# FishTankControllerV2.net
KiCad netlist of a schematic drawn in EAGLE
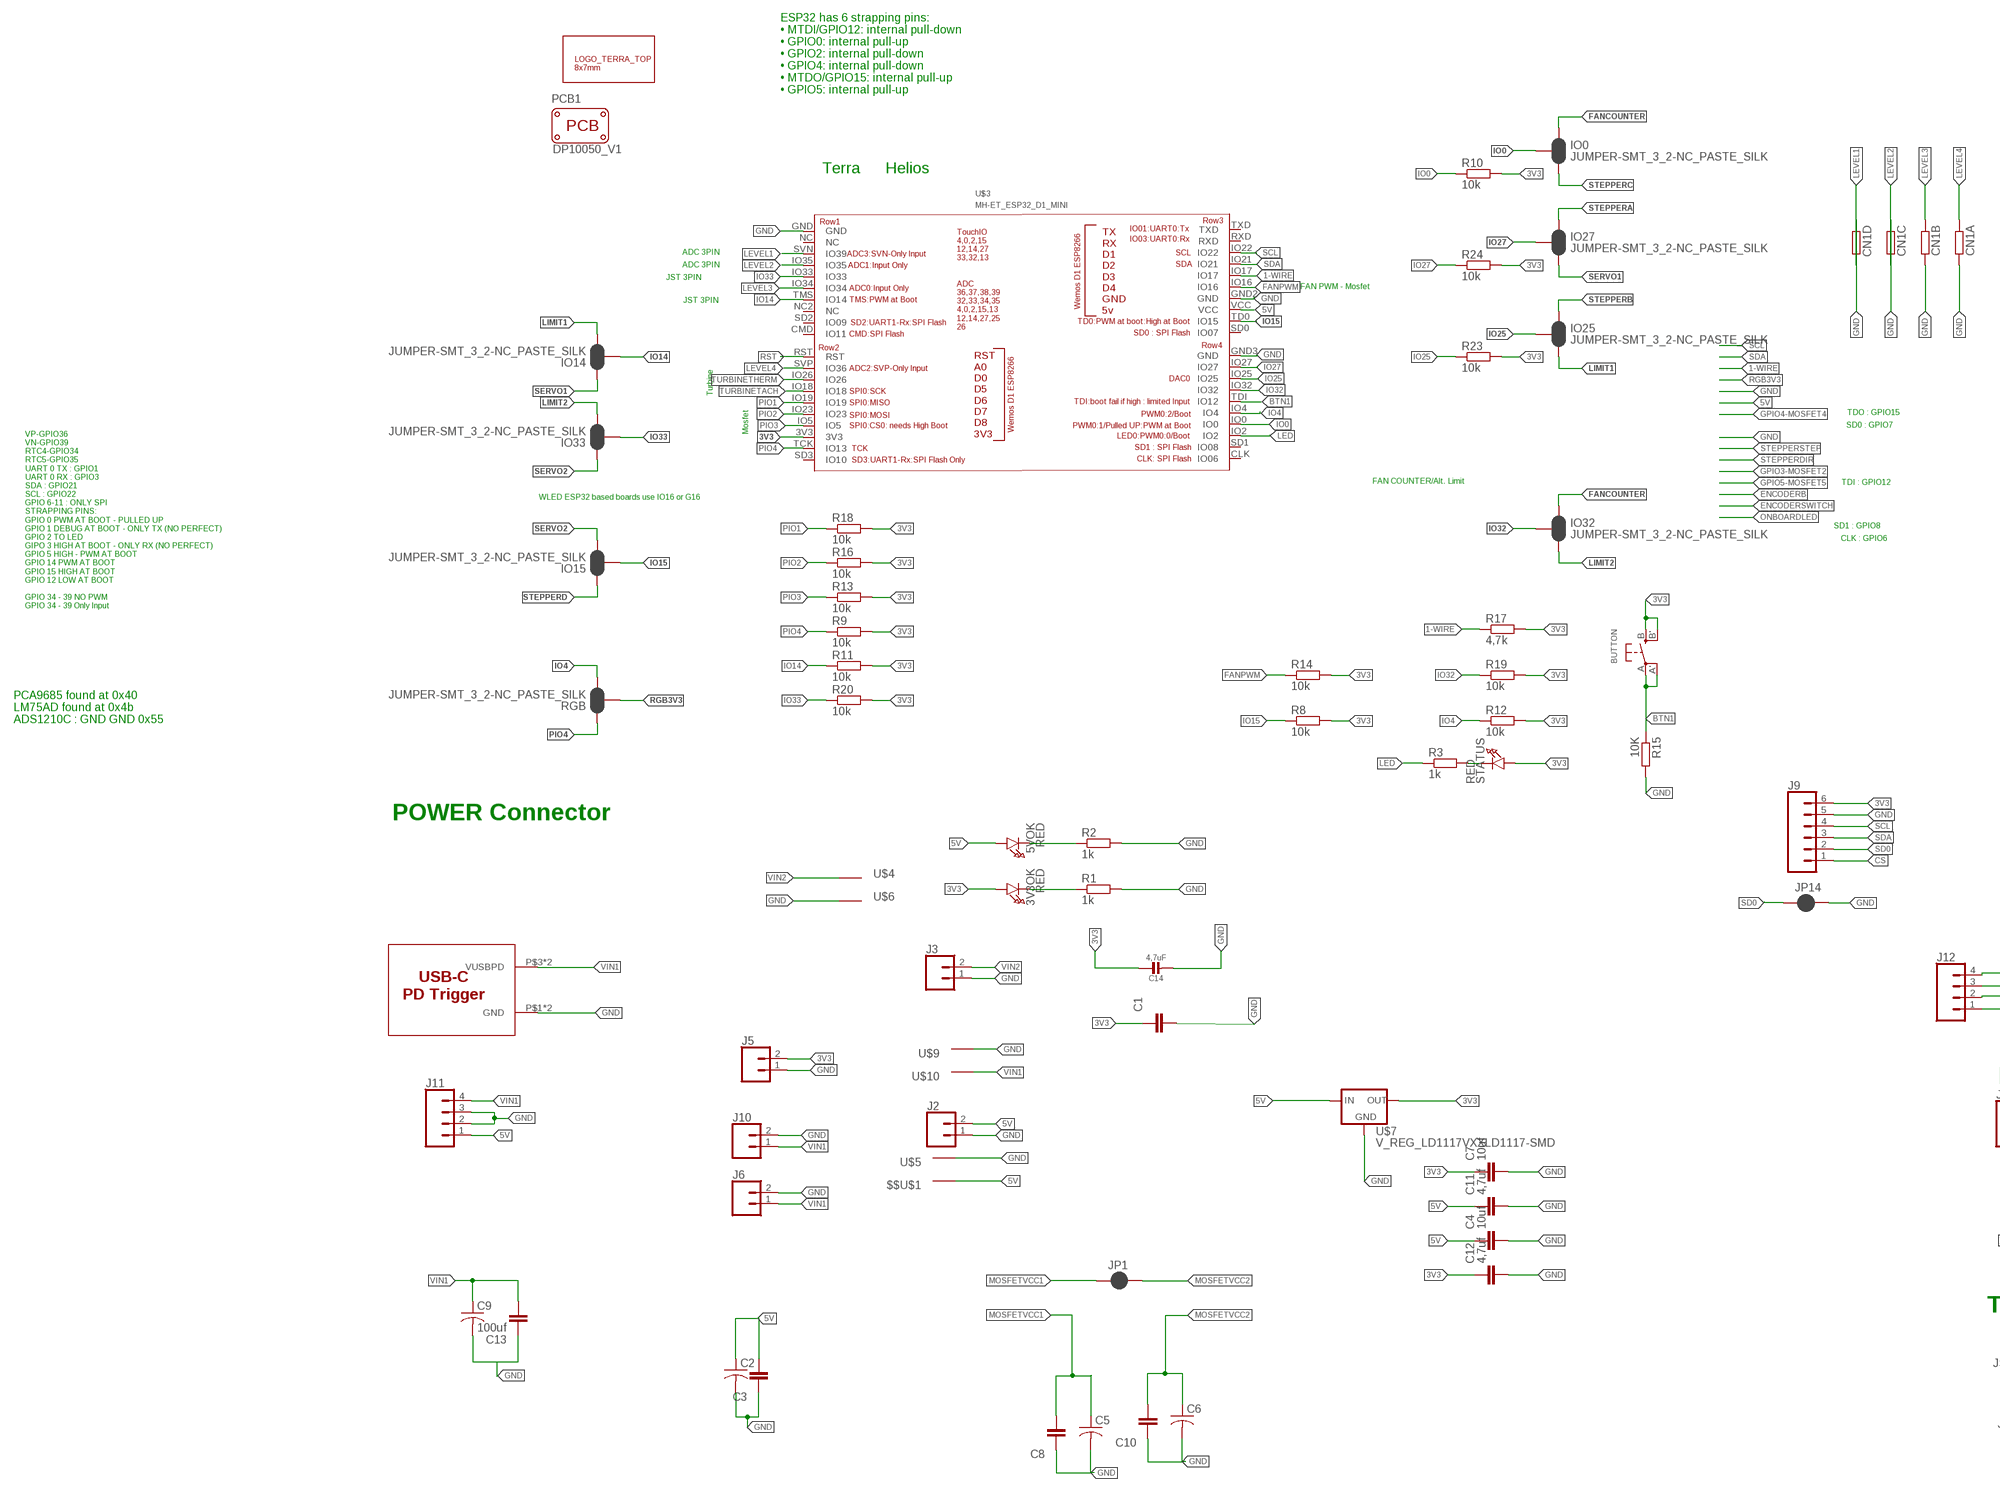
[diagram p0: schematic, sheet 1, part 1 of 2]
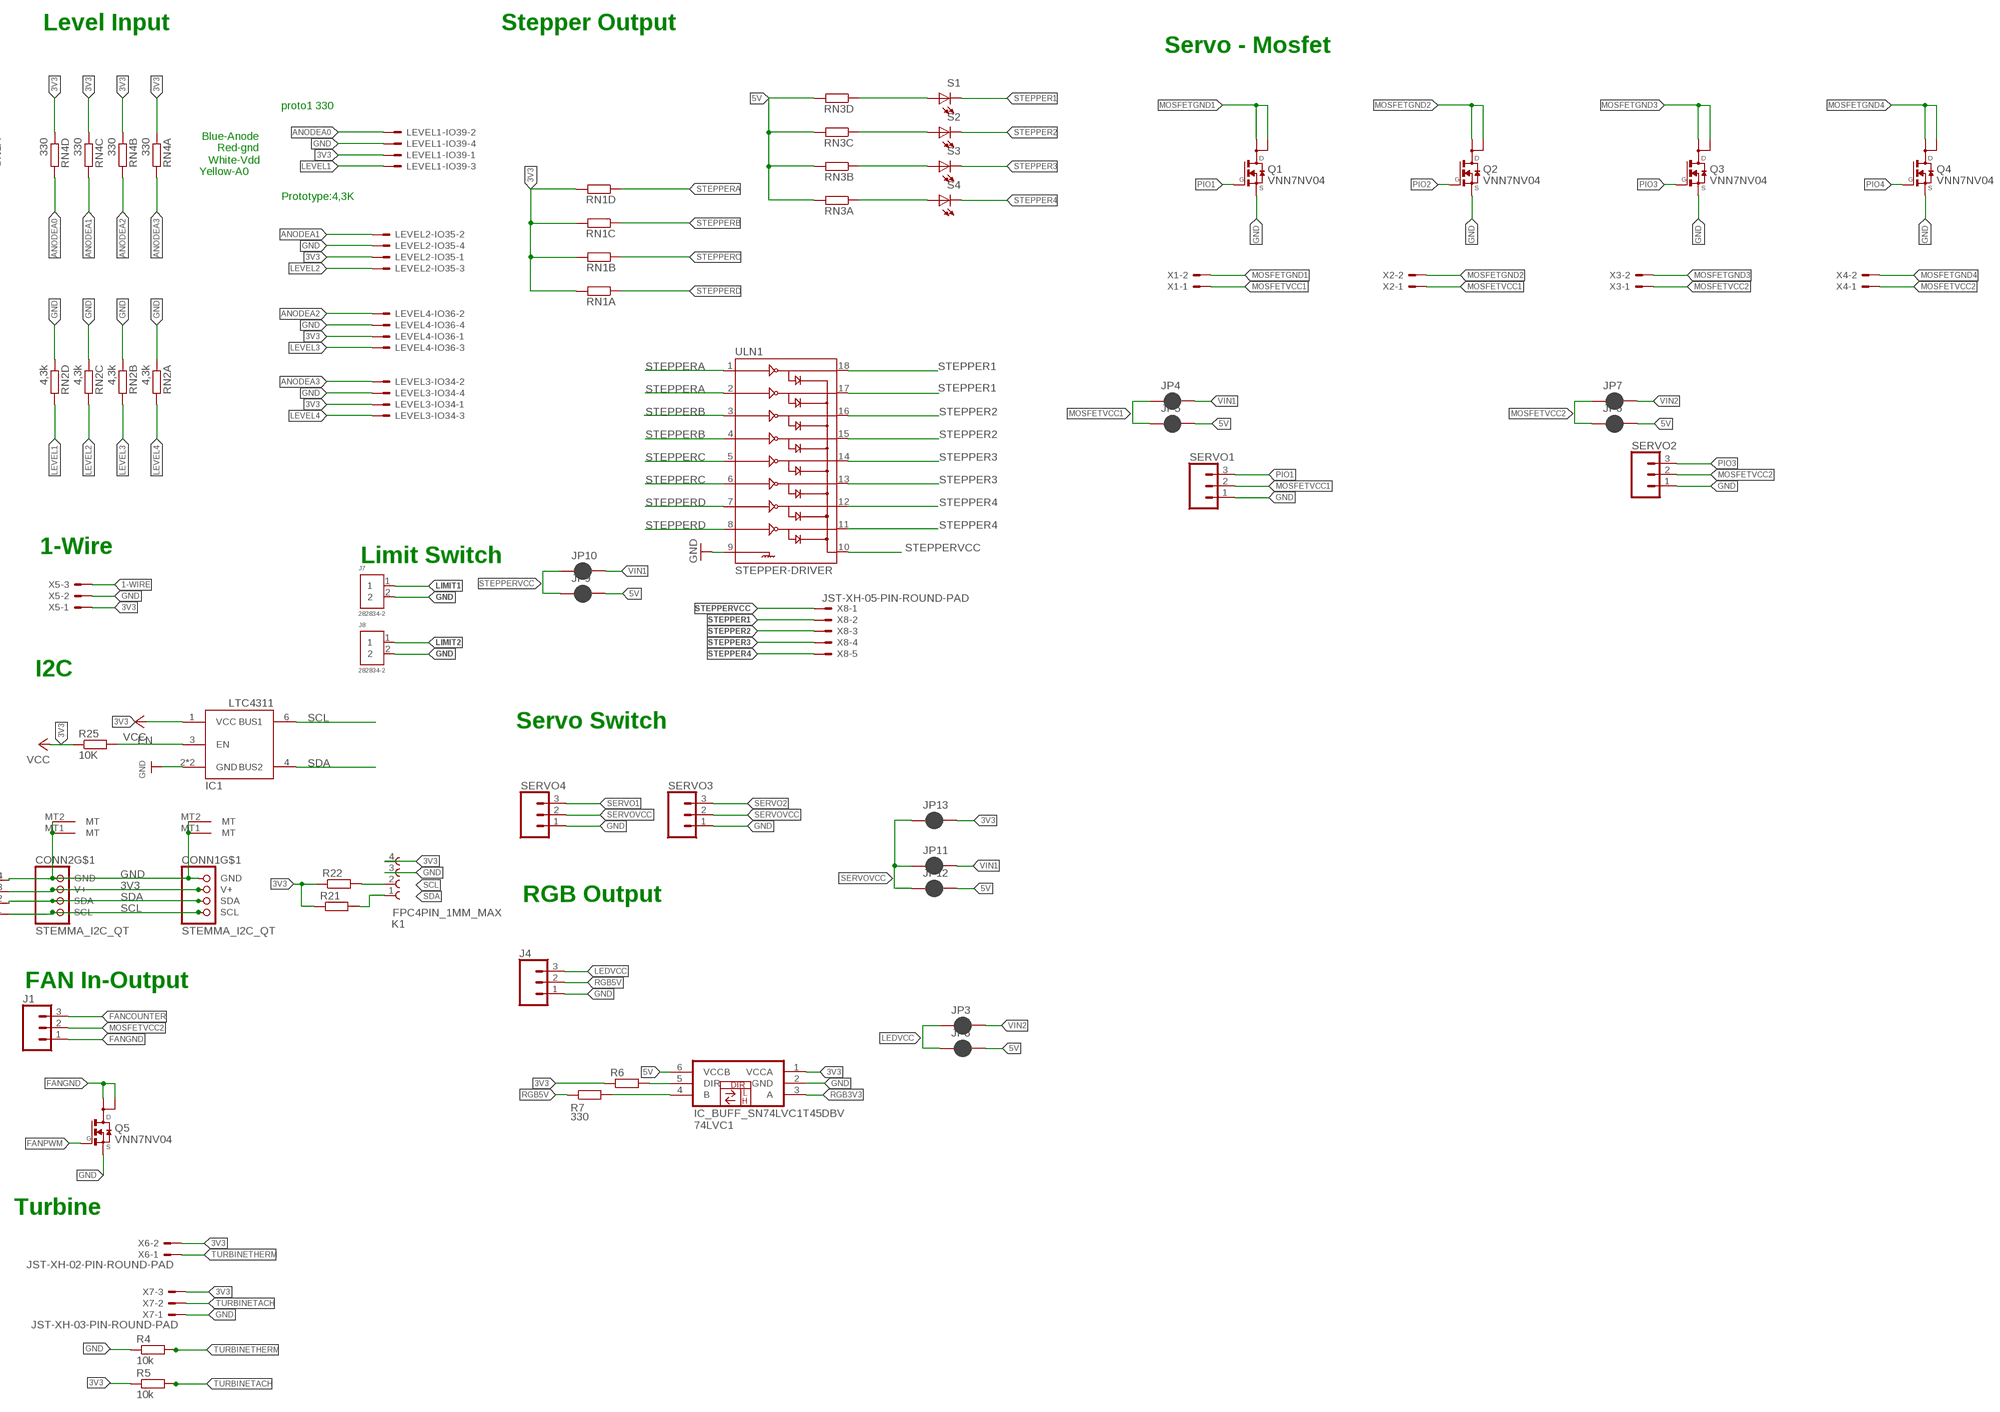
[diagram p1: schematic, sheet 1, part 2 of 2]

(export (version "E")
  (design (tool "Eeschema 10.0.6"))
  (components
    (comp (ref "$$U$1")
      (value "TESTHOOK")
      (footprint "eagle-import:TESTHOOK")
      (libsource (lib "eagle-import") (part "TESTHOOK"))
    )
    (comp (ref "3V3OK")
      (value "RED")
      (footprint "eagle-import:CHIPLED_0805")
      (libsource (lib "eagle-import") (part "LED0805"))
    )
    (comp (ref "5VOK")
      (value "RED")
      (footprint "eagle-import:CHIPLED_0805")
      (libsource (lib "eagle-import") (part "LED0805"))
    )
    (comp (ref "74LVC1")
      (value "IC_BUFF_SN74LVC1T45DBV")
      (footprint "eagle-import:DBV-R-PDSO-G6")
      (libsource (lib "eagle-import") (part "IC_BUFF_SN74LVC1T45DBV"))
    )
    (comp (ref "BUTTON")
      (value "KMR2")
      (footprint "eagle-import:BTN_KMR2_4.6X2.8")
      (libsource (lib "eagle-import") (part "SWITCH_TACT_SMT4.6X2.8"))
    )
    (comp (ref "C1")
      (value "CAPACITOR_NPOL-0805")
      (footprint "eagle-import:C805")
      (libsource (lib "eagle-import") (part "CAPACITOR_NPOL-0805"))
    )
    (comp (ref "C2")
      (value "C-USC1210")
      (footprint "eagle-import:C1210")
      (libsource (lib "eagle-import") (part "C-USC1210"))
    )
    (comp (ref "C3")
      (value "CAPACITOR_NPOL-0805")
      (footprint "eagle-import:C805")
      (libsource (lib "eagle-import") (part "CAPACITOR_NPOL-0805"))
    )
    (comp (ref "C4")
      (value "10uf")
      (footprint "eagle-import:C805")
      (libsource (lib "eagle-import") (part "CAPACITOR_NPOL-0805"))
    )
    (comp (ref "C5")
      (value "C-USC1210")
      (footprint "eagle-import:C1210")
      (libsource (lib "eagle-import") (part "C-USC1210"))
    )
    (comp (ref "C6")
      (value "C-USC1210")
      (footprint "eagle-import:C1210")
      (libsource (lib "eagle-import") (part "C-USC1210"))
    )
    (comp (ref "C7")
      (value "10uf")
      (footprint "eagle-import:C805")
      (libsource (lib "eagle-import") (part "CAPACITOR_NPOL-0805"))
    )
    (comp (ref "C8")
      (value "CAPACITOR_NPOL-0805")
      (footprint "eagle-import:C805")
      (libsource (lib "eagle-import") (part "CAPACITOR_NPOL-0805"))
    )
    (comp (ref "C9")
      (value "100uf")
      (footprint "eagle-import:C1210")
      (libsource (lib "eagle-import") (part "C-USC1210"))
    )
    (comp (ref "C10")
      (value "CAPACITOR_NPOL-0805")
      (footprint "eagle-import:C805")
      (libsource (lib "eagle-import") (part "CAPACITOR_NPOL-0805"))
    )
    (comp (ref "C11")
      (value "4,7uf")
      (footprint "eagle-import:C805")
      (libsource (lib "eagle-import") (part "CAPACITOR_NPOL-0805"))
    )
    (comp (ref "C12")
      (value "4,7uf")
      (footprint "eagle-import:C805")
      (libsource (lib "eagle-import") (part "CAPACITOR_NPOL-0805"))
    )
    (comp (ref "C13")
      (value "CAPACITOR_NPOL-0805")
      (footprint "eagle-import:C805")
      (libsource (lib "eagle-import") (part "CAPACITOR_NPOL-0805"))
    )
    (comp (ref "C14")
      (value "4,7uF")
      (footprint "eagle-import:0805-NO")
      (libsource (lib "eagle-import") (part "CAP_CERAMIC0805-NOOUTLINE"))
    )
    (comp (ref "CN1")
      (value "RESISTOR_ARRAY_4")
      (footprint "eagle-import:RN8P-4R-CRA06S")
      (libsource (lib "eagle-import") (part "RESISTOR_ARRAY_4"))
    )
    (comp (ref "CONN1")
      (value "STEMMA_I2C_QT")
      (footprint "eagle-import:JST_SH4")
      (libsource (lib "eagle-import") (part "STEMMA_I2C_QT"))
    )
    (comp (ref "CONN2")
      (value "STEMMA_I2C_QT")
      (footprint "eagle-import:JST_SH4")
      (libsource (lib "eagle-import") (part "STEMMA_I2C_QT"))
    )
    (comp (ref "IC1")
      (value "LTC4311_SC70")
      (footprint "eagle-import:SC70-6L")
      (libsource (lib "eagle-import") (part "LTC4311_SC70"))
    )
    (comp (ref "IO0")
      (value "JUMPER-SMT_3_2-NC_PASTE_SILK")
      (footprint "eagle-import:SMT-JUMPER_3_2-NC_PASTE_SILK")
      (libsource (lib "eagle-import") (part "JUMPER-SMT_3_2-NC_PASTE_SILK"))
    )
    (comp (ref "IO14")
      (value "JUMPER-SMT_3_2-NC_PASTE_SILK")
      (footprint "eagle-import:SMT-JUMPER_3_2-NC_PASTE_SILK")
      (libsource (lib "eagle-import") (part "JUMPER-SMT_3_2-NC_PASTE_SILK"))
    )
    (comp (ref "IO15")
      (value "JUMPER-SMT_3_2-NC_PASTE_SILK")
      (footprint "eagle-import:SMT-JUMPER_3_2-NC_PASTE_SILK")
      (libsource (lib "eagle-import") (part "JUMPER-SMT_3_2-NC_PASTE_SILK"))
    )
    (comp (ref "IO25")
      (value "JUMPER-SMT_3_2-NC_PASTE_SILK")
      (footprint "eagle-import:SMT-JUMPER_3_2-NC_PASTE_SILK")
      (libsource (lib "eagle-import") (part "JUMPER-SMT_3_2-NC_PASTE_SILK"))
    )
    (comp (ref "IO27")
      (value "JUMPER-SMT_3_2-NC_PASTE_SILK")
      (footprint "eagle-import:SMT-JUMPER_3_2-NC_PASTE_SILK")
      (libsource (lib "eagle-import") (part "JUMPER-SMT_3_2-NC_PASTE_SILK"))
    )
    (comp (ref "IO32")
      (value "JUMPER-SMT_3_2-NC_PASTE_SILK")
      (footprint "eagle-import:SMT-JUMPER_3_2-NC_PASTE_SILK")
      (libsource (lib "eagle-import") (part "JUMPER-SMT_3_2-NC_PASTE_SILK"))
    )
    (comp (ref "IO33")
      (value "JUMPER-SMT_3_2-NC_PASTE_SILK")
      (footprint "eagle-import:SMT-JUMPER_3_2-NC_PASTE_SILK")
      (libsource (lib "eagle-import") (part "JUMPER-SMT_3_2-NC_PASTE_SILK"))
    )
    (comp (ref "J1")
      (value "CONN_03POLAR")
      (footprint "eagle-import:MOLEX-1X3")
      (libsource (lib "eagle-import") (part "CONN_03POLAR"))
    )
    (comp (ref "J2")
      (value "CONN_02POLAR")
      (footprint "eagle-import:MOLEX-1X2")
      (libsource (lib "eagle-import") (part "CONN_02POLAR"))
    )
    (comp (ref "J3")
      (value "CONN_02POLAR")
      (footprint "eagle-import:MOLEX-1X2")
      (libsource (lib "eagle-import") (part "CONN_02POLAR"))
    )
    (comp (ref "J4")
      (value "CONN_03SCREW")
      (footprint "eagle-import:SCREWTERMINAL-3.5MM-3")
      (libsource (lib "eagle-import") (part "CONN_03SCREW"))
    )
    (comp (ref "J5")
      (value "CONN_02POLAR")
      (footprint "eagle-import:MOLEX-1X2")
      (libsource (lib "eagle-import") (part "CONN_02POLAR"))
    )
    (comp (ref "J6")
      (value "CONN_023.5MM")
      (footprint "eagle-import:SCREWTERMINAL-3.5MM-2")
      (libsource (lib "eagle-import") (part "CONN_023.5MM"))
    )
    (comp (ref "J7")
      (value "282834-2")
      (footprint "eagle-import:CONN_282834-2")
      (fields (field (name "MF") "TE Connectivity"))
      (libsource (lib "eagle-import") (part "282834-2"))
    )
    (comp (ref "J8")
      (value "282834-2")
      (footprint "eagle-import:CONN_282834-2")
      (fields (field (name "MF") "TE Connectivity"))
      (libsource (lib "eagle-import") (part "282834-2"))
    )
    (comp (ref "J9")
      (value "CONN_06NO_SILK_FEMALE_PTH")
      (footprint "eagle-import:1X06_NO_SILK")
      (libsource (lib "eagle-import") (part "CONN_06NO_SILK_FEMALE_PTH"))
    )
    (comp (ref "J10")
      (value "CONN_023.5MM")
      (footprint "eagle-import:SCREWTERMINAL-3.5MM-2")
      (libsource (lib "eagle-import") (part "CONN_023.5MM"))
    )
    (comp (ref "J11")
      (value "CONN_04")
      (footprint "eagle-import:1X04")
      (libsource (lib "eagle-import") (part "CONN_04"))
    )
    (comp (ref "J12")
      (value "CONN_04JST-PH-4-1.0MM")
      (footprint "eagle-import:JST-4-SMD-VERT-1.0MM")
      (libsource (lib "eagle-import") (part "CONN_04JST-PH-4-1.0MM"))
    )
    (comp (ref "JP1")
      (value "JUMPER-SMT_2_NC_PASTE_SILK")
      (footprint "eagle-import:SMT-JUMPER_2_NC_PASTE_SILK")
      (libsource (lib "eagle-import") (part "JUMPER-SMT_2_NC_PASTE_SILK"))
    )
    (comp (ref "JP3")
      (value "JUMPER-SMT_2_NC_PASTE_SILK")
      (footprint "eagle-import:SMT-JUMPER_2_NC_PASTE_SILK")
      (libsource (lib "eagle-import") (part "JUMPER-SMT_2_NC_PASTE_SILK"))
    )
    (comp (ref "JP4")
      (value "JUMPER-SMT_2_NC_PASTE_SILK")
      (footprint "eagle-import:SMT-JUMPER_2_NC_PASTE_SILK")
      (libsource (lib "eagle-import") (part "JUMPER-SMT_2_NC_PASTE_SILK"))
    )
    (comp (ref "JP5")
      (value "JUMPER-SMT_2_NC_PASTE_SILK")
      (footprint "eagle-import:SMT-JUMPER_2_NC_PASTE_SILK")
      (libsource (lib "eagle-import") (part "JUMPER-SMT_2_NC_PASTE_SILK"))
    )
    (comp (ref "JP6")
      (value "JUMPER-SMT_2_NC_PASTE_SILK")
      (footprint "eagle-import:SMT-JUMPER_2_NC_PASTE_SILK")
      (libsource (lib "eagle-import") (part "JUMPER-SMT_2_NC_PASTE_SILK"))
    )
    (comp (ref "JP7")
      (value "JUMPER-SMT_2_NC_PASTE_SILK")
      (footprint "eagle-import:SMT-JUMPER_2_NC_PASTE_SILK")
      (libsource (lib "eagle-import") (part "JUMPER-SMT_2_NC_PASTE_SILK"))
    )
    (comp (ref "JP8")
      (value "JUMPER-SMT_2_NC_PASTE_SILK")
      (footprint "eagle-import:SMT-JUMPER_2_NC_PASTE_SILK")
      (libsource (lib "eagle-import") (part "JUMPER-SMT_2_NC_PASTE_SILK"))
    )
    (comp (ref "JP9")
      (value "JUMPER-SMT_2_NC_PASTE_SILK")
      (footprint "eagle-import:SMT-JUMPER_2_NC_PASTE_SILK")
      (libsource (lib "eagle-import") (part "JUMPER-SMT_2_NC_PASTE_SILK"))
    )
    (comp (ref "JP10")
      (value "JUMPER-SMT_2_NC_PASTE_SILK")
      (footprint "eagle-import:SMT-JUMPER_2_NC_PASTE_SILK")
      (libsource (lib "eagle-import") (part "JUMPER-SMT_2_NC_PASTE_SILK"))
    )
    (comp (ref "JP11")
      (value "JUMPER-SMT_2_NC_PASTE_SILK")
      (footprint "eagle-import:SMT-JUMPER_2_NC_PASTE_SILK")
      (libsource (lib "eagle-import") (part "JUMPER-SMT_2_NC_PASTE_SILK"))
    )
    (comp (ref "JP12")
      (value "JUMPER-SMT_2_NC_PASTE_SILK")
      (footprint "eagle-import:SMT-JUMPER_2_NC_PASTE_SILK")
      (libsource (lib "eagle-import") (part "JUMPER-SMT_2_NC_PASTE_SILK"))
    )
    (comp (ref "JP13")
      (value "JUMPER-SMT_2_NC_PASTE_SILK")
      (footprint "eagle-import:SMT-JUMPER_2_NC_PASTE_SILK")
      (libsource (lib "eagle-import") (part "JUMPER-SMT_2_NC_PASTE_SILK"))
    )
    (comp (ref "JP14")
      (value "JUMPER-SMT_2_NC_PASTE_SILK")
      (footprint "eagle-import:SMT-JUMPER_2_NC_PASTE_SILK")
      (libsource (lib "eagle-import") (part "JUMPER-SMT_2_NC_PASTE_SILK"))
    )
    (comp (ref "K1")
      (value "FPC4PIN_1MM_MAX")
      (footprint "eagle-import:FPC_CONN_DOC_4PIN_ENLARGED")
      (libsource (lib "eagle-import") (part "FPC4PIN_1MM_MAX"))
    )
    (comp (ref "LEVEL1-IO39")
      (value "JST-XH-04-PIN-ROUND-PAD")
      (footprint "eagle-import:JST-XH-04-PACKAGE-ROUND-PAD")
      (libsource (lib "eagle-import") (part "JST-XH-04-PIN-ROUND-PAD"))
    )
    (comp (ref "LEVEL2-IO35")
      (value "JST-XH-04-PIN-ROUND-PAD")
      (footprint "eagle-import:JST-XH-04-PACKAGE-ROUND-PAD")
      (libsource (lib "eagle-import") (part "JST-XH-04-PIN-ROUND-PAD"))
    )
    (comp (ref "LEVEL3-IO34")
      (value "JST-XH-04-PIN-ROUND-PAD")
      (footprint "eagle-import:JST-XH-04-PACKAGE-ROUND-PAD")
      (libsource (lib "eagle-import") (part "JST-XH-04-PIN-ROUND-PAD"))
    )
    (comp (ref "LEVEL4-IO36")
      (value "JST-XH-04-PIN-ROUND-PAD")
      (footprint "eagle-import:JST-XH-04-PACKAGE-ROUND-PAD")
      (libsource (lib "eagle-import") (part "JST-XH-04-PIN-ROUND-PAD"))
    )
    (comp (ref "PCB1")
      (value "PCB_DP_RECTANGLE-50X100")
      (footprint "eagle-import:DP10050_V1")
      (fields (field (name "PCB_SIZE") "DP10050_V1"))
      (libsource (lib "eagle-import") (part "PCB_DP_RECTANGLE-50X100"))
    )
    (comp (ref "Q1")
      (value "VNN7NV04")
      (footprint "eagle-import:SOT223")
      (fields (field (name "MF") "STMicroelectronics"))
      (libsource (lib "eagle-import") (part "VNN7NV04"))
    )
    (comp (ref "Q2")
      (value "VNN7NV04")
      (footprint "eagle-import:SOT223")
      (fields (field (name "MF") "STMicroelectronics"))
      (libsource (lib "eagle-import") (part "VNN7NV04"))
    )
    (comp (ref "Q3")
      (value "VNN7NV04")
      (footprint "eagle-import:SOT223")
      (fields (field (name "MF") "STMicroelectronics"))
      (libsource (lib "eagle-import") (part "VNN7NV04"))
    )
    (comp (ref "Q4")
      (value "VNN7NV04")
      (footprint "eagle-import:SOT223")
      (fields (field (name "MF") "STMicroelectronics"))
      (libsource (lib "eagle-import") (part "VNN7NV04"))
    )
    (comp (ref "Q5")
      (value "VNN7NV04")
      (footprint "eagle-import:SOT223")
      (fields (field (name "MF") "STMicroelectronics"))
      (libsource (lib "eagle-import") (part "VNN7NV04"))
    )
    (comp (ref "R1")
      (value "1k")
      (footprint "eagle-import:R805")
      (libsource (lib "eagle-import") (part "RESISTOR-0805R805"))
    )
    (comp (ref "R2")
      (value "1k")
      (footprint "eagle-import:R805")
      (libsource (lib "eagle-import") (part "RESISTOR-0805R805"))
    )
    (comp (ref "R3")
      (value "1k")
      (footprint "eagle-import:R805")
      (libsource (lib "eagle-import") (part "RESISTOR-0805R805"))
    )
    (comp (ref "R4")
      (value "10k")
      (footprint "eagle-import:R805")
      (libsource (lib "eagle-import") (part "RESISTOR-0805R805"))
    )
    (comp (ref "R5")
      (value "10k")
      (footprint "eagle-import:R805")
      (libsource (lib "eagle-import") (part "RESISTOR-0805R805"))
    )
    (comp (ref "R6")
      (value "RESISTORR805-0805")
      (footprint "eagle-import:R805")
      (libsource (lib "eagle-import") (part "RESISTOR-0805R805"))
    )
    (comp (ref "R7")
      (value "330")
      (footprint "eagle-import:R805")
      (libsource (lib "eagle-import") (part "RESISTOR-0805R805"))
    )
    (comp (ref "R8")
      (value "10k")
      (footprint "eagle-import:R805")
      (libsource (lib "eagle-import") (part "RESISTOR-0805R805"))
    )
    (comp (ref "R9")
      (value "10k")
      (footprint "eagle-import:R805")
      (libsource (lib "eagle-import") (part "RESISTOR-0805R805"))
    )
    (comp (ref "R10")
      (value "10k")
      (footprint "eagle-import:R805")
      (libsource (lib "eagle-import") (part "RESISTOR-0805R805"))
    )
    (comp (ref "R11")
      (value "10k")
      (footprint "eagle-import:R805")
      (libsource (lib "eagle-import") (part "RESISTOR-0805R805"))
    )
    (comp (ref "R12")
      (value "10k")
      (footprint "eagle-import:R805")
      (libsource (lib "eagle-import") (part "RESISTOR-0805R805"))
    )
    (comp (ref "R13")
      (value "10k")
      (footprint "eagle-import:R805")
      (libsource (lib "eagle-import") (part "RESISTOR-0805R805"))
    )
    (comp (ref "R14")
      (value "10k")
      (footprint "eagle-import:R805")
      (libsource (lib "eagle-import") (part "RESISTOR-0805R805"))
    )
    (comp (ref "R15")
      (value "10K")
      (footprint "eagle-import:R805")
      (libsource (lib "eagle-import") (part "RESISTOR-0805R805"))
    )
    (comp (ref "R16")
      (value "10k")
      (footprint "eagle-import:R805")
      (libsource (lib "eagle-import") (part "RESISTOR-0805R805"))
    )
    (comp (ref "R17")
      (value "4,7k")
      (footprint "eagle-import:R805")
      (libsource (lib "eagle-import") (part "RESISTOR-0805R805"))
    )
    (comp (ref "R18")
      (value "10k")
      (footprint "eagle-import:R805")
      (libsource (lib "eagle-import") (part "RESISTOR-0805R805"))
    )
    (comp (ref "R19")
      (value "10k")
      (footprint "eagle-import:R805")
      (libsource (lib "eagle-import") (part "RESISTOR-0805R805"))
    )
    (comp (ref "R20")
      (value "10k")
      (footprint "eagle-import:R805")
      (libsource (lib "eagle-import") (part "RESISTOR-0805R805"))
    )
    (comp (ref "R21")
      (value "RESISTORR805-0805")
      (footprint "eagle-import:R805")
      (libsource (lib "eagle-import") (part "RESISTOR-0805R805"))
    )
    (comp (ref "R22")
      (value "RESISTORR805-0805")
      (footprint "eagle-import:R805")
      (libsource (lib "eagle-import") (part "RESISTOR-0805R805"))
    )
    (comp (ref "R23")
      (value "10k")
      (footprint "eagle-import:R805")
      (libsource (lib "eagle-import") (part "RESISTOR-0805R805"))
    )
    (comp (ref "R24")
      (value "10k")
      (footprint "eagle-import:R805")
      (libsource (lib "eagle-import") (part "RESISTOR-0805R805"))
    )
    (comp (ref "R25")
      (value "10K")
      (footprint "eagle-import:R805")
      (libsource (lib "eagle-import") (part "RESISTOR-0805R805"))
    )
    (comp (ref "RGB")
      (value "JUMPER-SMT_3_2-NC_PASTE_SILK")
      (footprint "eagle-import:SMT-JUMPER_3_2-NC_PASTE_SILK")
      (libsource (lib "eagle-import") (part "JUMPER-SMT_3_2-NC_PASTE_SILK"))
    )
    (comp (ref "RN1")
      (value "RESISTOR_ARRAY_4")
      (footprint "eagle-import:RN8P-4R-CRA06S")
      (libsource (lib "eagle-import") (part "RESISTOR_ARRAY_4"))
    )
    (comp (ref "RN2")
      (value "4,3k")
      (footprint "eagle-import:RN8P-4R-CRA06S")
      (libsource (lib "eagle-import") (part "RESISTOR_ARRAY_4"))
    )
    (comp (ref "RN3")
      (value "RESISTOR_ARRAY_4")
      (footprint "eagle-import:RN8P-4R-CRA06S")
      (libsource (lib "eagle-import") (part "RESISTOR_ARRAY_4"))
    )
    (comp (ref "RN4")
      (value "330")
      (footprint "eagle-import:RN8P-4R-CRA06S")
      (libsource (lib "eagle-import") (part "RESISTOR_ARRAY_4"))
    )
    (comp (ref "S1")
      (value "LED-0805")
      (footprint "eagle-import:LED-805")
      (libsource (lib "eagle-import") (part "LED-0805"))
    )
    (comp (ref "S2")
      (value "LED-0805")
      (footprint "eagle-import:LED-805")
      (libsource (lib "eagle-import") (part "LED-0805"))
    )
    (comp (ref "S3")
      (value "LED-0805")
      (footprint "eagle-import:LED-805")
      (libsource (lib "eagle-import") (part "LED-0805"))
    )
    (comp (ref "S4")
      (value "LED-0805")
      (footprint "eagle-import:LED-805")
      (libsource (lib "eagle-import") (part "LED-0805"))
    )
    (comp (ref "SERVO1")
      (value "CONN_03POLAR")
      (footprint "eagle-import:MOLEX-1X3")
      (libsource (lib "eagle-import") (part "CONN_03POLAR"))
    )
    (comp (ref "SERVO2")
      (value "CONN_03POLAR")
      (footprint "eagle-import:MOLEX-1X3")
      (libsource (lib "eagle-import") (part "CONN_03POLAR"))
    )
    (comp (ref "SERVO3")
      (value "CONN_03POLAR")
      (footprint "eagle-import:MOLEX-1X3")
      (libsource (lib "eagle-import") (part "CONN_03POLAR"))
    )
    (comp (ref "SERVO4")
      (value "CONN_03POLAR")
      (footprint "eagle-import:MOLEX-1X3")
      (libsource (lib "eagle-import") (part "CONN_03POLAR"))
    )
    (comp (ref "STATUS")
      (value "RED")
      (footprint "eagle-import:CHIPLED_0805")
      (libsource (lib "eagle-import") (part "LED0805"))
    )
    (comp (ref "U$1")
      (value "LOGOTOPTERRA")
      (footprint "eagle-import:LOGOTOPTERRA")
      (libsource (lib "eagle-import") (part "LOGOTOPTERRA"))
    )
    (comp (ref "U$3")
      (value "MH-ET_ESP32_D1_MINI")
      (footprint "eagle-import:MH-ET_ESP32_D1_MINI")
      (libsource (lib "eagle-import") (part "MH-ET_ESP32_D1_MINI"))
    )
    (comp (ref "U$4")
      (value "TESTHOOK")
      (footprint "eagle-import:TESTHOOK")
      (libsource (lib "eagle-import") (part "TESTHOOK"))
    )
    (comp (ref "U$5")
      (value "TESTHOOK")
      (footprint "eagle-import:TESTHOOK")
      (libsource (lib "eagle-import") (part "TESTHOOK"))
    )
    (comp (ref "U$6")
      (value "TESTHOOK")
      (footprint "eagle-import:TESTHOOK")
      (libsource (lib "eagle-import") (part "TESTHOOK"))
    )
    (comp (ref "U$7")
      (value "V_REG_LD1117VXXLD1117-SMD")
      (footprint "eagle-import:SOT223")
      (libsource (lib "eagle-import") (part "V_REG_LD1117VXXLD1117-SMD"))
    )
    (comp (ref "U$8")
      (value "USB_PD_TRIGGER")
      (footprint "eagle-import:USB-PDTRIGGER")
      (libsource (lib "eagle-import") (part "USB_PD_TRIGGER"))
    )
    (comp (ref "U$9")
      (value "TESTHOOK")
      (footprint "eagle-import:TESTHOOK")
      (libsource (lib "eagle-import") (part "TESTHOOK"))
    )
    (comp (ref "U$10")
      (value "TESTHOOK")
      (footprint "eagle-import:TESTHOOK")
      (libsource (lib "eagle-import") (part "TESTHOOK"))
    )
    (comp (ref "ULN1")
      (value "STEPPER-DRIVER")
      (footprint "eagle-import:SO18L")
      (libsource (lib "eagle-import") (part "ULN2803SOICW"))
    )
    (comp (ref "X1")
      (value "JST-XH-02-PIN-ROUND-PAD")
      (footprint "eagle-import:JST-XH-02-PACKAGE-ROUND-PAD")
      (libsource (lib "eagle-import") (part "JST-XH-02-PIN-ROUND-PAD"))
    )
    (comp (ref "X2")
      (value "JST-XH-02-PIN-ROUND-PAD")
      (footprint "eagle-import:JST-XH-02-PACKAGE-ROUND-PAD")
      (libsource (lib "eagle-import") (part "JST-XH-02-PIN-ROUND-PAD"))
    )
    (comp (ref "X3")
      (value "JST-XH-02-PIN-ROUND-PAD")
      (footprint "eagle-import:JST-XH-02-PACKAGE-ROUND-PAD")
      (libsource (lib "eagle-import") (part "JST-XH-02-PIN-ROUND-PAD"))
    )
    (comp (ref "X4")
      (value "JST-XH-02-PIN-ROUND-PAD")
      (footprint "eagle-import:JST-XH-02-PACKAGE-ROUND-PAD")
      (libsource (lib "eagle-import") (part "JST-XH-02-PIN-ROUND-PAD"))
    )
    (comp (ref "X5")
      (value "JST-XH-03-PIN-ROUND-PAD")
      (footprint "eagle-import:JST-XH-03-PACKAGE-ROUND-PAD")
      (libsource (lib "eagle-import") (part "JST-XH-03-PIN-ROUND-PAD"))
    )
    (comp (ref "X6")
      (value "JST-XH-02-PIN-ROUND-PAD")
      (footprint "eagle-import:JST-XH-02-PACKAGE-ROUND-PAD")
      (libsource (lib "eagle-import") (part "JST-XH-02-PIN-ROUND-PAD"))
    )
    (comp (ref "X7")
      (value "JST-XH-03-PIN-ROUND-PAD")
      (footprint "eagle-import:JST-XH-03-PACKAGE-ROUND-PAD")
      (libsource (lib "eagle-import") (part "JST-XH-03-PIN-ROUND-PAD"))
    )
    (comp (ref "X8")
      (value "JST-XH-05-PIN-ROUND-PAD")
      (footprint "eagle-import:JST-XH-05-PACKAGE-ROUND-PAD")
      (libsource (lib "eagle-import") (part "JST-XH-05-PIN-ROUND-PAD"))
    )
  )
  (nets
    (net (code "1") (name "/EN") (class "Default")
      (node (ref "IC1") (pin "3") (pinfunction "EN_3") (pintype "input"))
      (node (ref "R25") (pin "2") (pinfunction "2_2") (pintype "passive"))
    )
    (net (code "2") (name "1-WIRE") (class "Default")
      (node (ref "R17") (pin "1") (pinfunction "1_1") (pintype "passive"))
      (node (ref "U$3") (pin "IO17") (pinfunction "IO17_IO17") (pintype "bidirectional"))
      (node (ref "X5") (pin "3") (pinfunction "S_3") (pintype "passive"))
    )
    (net (code "3") (name "3V3") (class "Default")
      (node (ref "3V3OK") (pin "A") (pinfunction "A_A") (pintype "passive"))
      (node (ref "74LVC1") (pin "1") (pinfunction "VCCA_1") (pintype "power_in"))
      (node (ref "BUTTON") (pin "B") (pinfunction "S_B") (pintype "passive"))
      (node (ref "BUTTON") (pin "B'") (pinfunction "S1_B'") (pintype "passive"))
      (node (ref "C1") (pin "1") (pinfunction "1_1") (pintype "passive"))
      (node (ref "C12") (pin "1") (pinfunction "1_1") (pintype "passive"))
      (node (ref "C14") (pin "1") (pinfunction "1_1") (pintype "passive"))
      (node (ref "C7") (pin "1") (pinfunction "1_1") (pintype "passive"))
      (node (ref "CONN1") (pin "2") (pinfunction "V+_2") (pintype "passive"))
      (node (ref "CONN2") (pin "2") (pinfunction "V+_2") (pintype "passive"))
      (node (ref "IC1") (pin "1") (pinfunction "VCC_1") (pintype "power_in"))
      (node (ref "J12") (pin "3") (pinfunction "3_3") (pintype "passive"))
      (node (ref "J5") (pin "2") (pinfunction "2_2") (pintype "passive"))
      (node (ref "J9") (pin "6") (pinfunction "6_6") (pintype "passive"))
      (node (ref "JP13") (pin "2") (pinfunction "2_2") (pintype "passive"))
      (node (ref "K1") (pin "4") (pinfunction "4_4") (pintype "passive"))
      (node (ref "LEVEL1-IO39") (pin "1") (pinfunction "S_1") (pintype "passive"))
      (node (ref "LEVEL2-IO35") (pin "1") (pinfunction "S_1") (pintype "passive"))
      (node (ref "LEVEL3-IO34") (pin "1") (pinfunction "S_1") (pintype "passive"))
      (node (ref "LEVEL4-IO36") (pin "1") (pinfunction "S_1") (pintype "passive"))
      (node (ref "R10") (pin "2") (pinfunction "2_2") (pintype "passive"))
      (node (ref "R11") (pin "2") (pinfunction "2_2") (pintype "passive"))
      (node (ref "R12") (pin "2") (pinfunction "2_2") (pintype "passive"))
      (node (ref "R13") (pin "2") (pinfunction "2_2") (pintype "passive"))
      (node (ref "R14") (pin "2") (pinfunction "2_2") (pintype "passive"))
      (node (ref "R16") (pin "2") (pinfunction "2_2") (pintype "passive"))
      (node (ref "R17") (pin "2") (pinfunction "2_2") (pintype "passive"))
      (node (ref "R18") (pin "2") (pinfunction "2_2") (pintype "passive"))
      (node (ref "R19") (pin "2") (pinfunction "2_2") (pintype "passive"))
      (node (ref "R20") (pin "2") (pinfunction "2_2") (pintype "passive"))
      (node (ref "R21") (pin "1") (pinfunction "1_1") (pintype "passive"))
      (node (ref "R22") (pin "1") (pinfunction "1_1") (pintype "passive"))
      (node (ref "R23") (pin "2") (pinfunction "2_2") (pintype "passive"))
      (node (ref "R24") (pin "2") (pinfunction "2_2") (pintype "passive"))
      (node (ref "R25") (pin "1") (pinfunction "1_1") (pintype "passive"))
      (node (ref "R5") (pin "1") (pinfunction "1_1") (pintype "passive"))
      (node (ref "R6") (pin "1") (pinfunction "1_1") (pintype "passive"))
      (node (ref "R8") (pin "2") (pinfunction "2_2") (pintype "passive"))
      (node (ref "R9") (pin "2") (pinfunction "2_2") (pintype "passive"))
      (node (ref "RN1") (pin "5") (pinfunction "2_5") (pintype "passive"))
      (node (ref "RN1") (pin "6") (pinfunction "2_6") (pintype "passive"))
      (node (ref "RN1") (pin "7") (pinfunction "2_7") (pintype "passive"))
      (node (ref "RN1") (pin "8") (pinfunction "2_8") (pintype "passive"))
      (node (ref "RN4") (pin "1") (pinfunction "1_1") (pintype "passive"))
      (node (ref "RN4") (pin "2") (pinfunction "1_2") (pintype "passive"))
      (node (ref "RN4") (pin "3") (pinfunction "1_3") (pintype "passive"))
      (node (ref "RN4") (pin "4") (pinfunction "1_4") (pintype "passive"))
      (node (ref "STATUS") (pin "A") (pinfunction "A_A") (pintype "passive"))
      (node (ref "U$3") (pin "3V3") (pinfunction "3V3_3V3") (pintype "bidirectional"))
      (node (ref "U$7") (pin "2") (pinfunction "OUT_2") (pintype "passive"))
      (node (ref "X5") (pin "1") (pinfunction "S_1") (pintype "passive"))
      (node (ref "X6") (pin "2") (pinfunction "S_2") (pintype "passive"))
      (node (ref "X7") (pin "3") (pinfunction "S_3") (pintype "passive"))
    )
    (net (code "4") (name "5V") (class "Default")
      (node (ref "$$U$1") (pin "P$1") (pinfunction "P$1_P$1") (pintype "bidirectional"))
      (node (ref "5VOK") (pin "A") (pinfunction "A_A") (pintype "passive"))
      (node (ref "74LVC1") (pin "6") (pinfunction "VCCB_6") (pintype "power_in"))
      (node (ref "C11") (pin "1") (pinfunction "1_1") (pintype "passive"))
      (node (ref "C2") (pin "1") (pinfunction "1_1") (pintype "passive"))
      (node (ref "C3") (pin "2") (pinfunction "2_2") (pintype "passive"))
      (node (ref "C4") (pin "1") (pinfunction "1_1") (pintype "passive"))
      (node (ref "J11") (pin "1") (pinfunction "1_1") (pintype "passive"))
      (node (ref "J2") (pin "2") (pinfunction "2_2") (pintype "passive"))
      (node (ref "JP12") (pin "2") (pinfunction "2_2") (pintype "passive"))
      (node (ref "JP5") (pin "2") (pinfunction "2_2") (pintype "passive"))
      (node (ref "JP6") (pin "2") (pinfunction "2_2") (pintype "passive"))
      (node (ref "JP8") (pin "2") (pinfunction "2_2") (pintype "passive"))
      (node (ref "JP9") (pin "2") (pinfunction "2_2") (pintype "passive"))
      (node (ref "RN3") (pin "5") (pinfunction "2_5") (pintype "passive"))
      (node (ref "RN3") (pin "6") (pinfunction "2_6") (pintype "passive"))
      (node (ref "RN3") (pin "7") (pinfunction "2_7") (pintype "passive"))
      (node (ref "RN3") (pin "8") (pinfunction "2_8") (pintype "passive"))
      (node (ref "U$3") (pin "VCC") (pinfunction "VCC_VCC") (pintype "bidirectional"))
      (node (ref "U$7") (pin "3") (pinfunction "IN_3") (pintype "input"))
    )
    (net (code "5") (name "ANODEA0") (class "Default")
      (node (ref "LEVEL1-IO39") (pin "2") (pinfunction "S_2") (pintype "passive"))
      (node (ref "RN4") (pin "5") (pinfunction "2_5") (pintype "passive"))
    )
    (net (code "6") (name "ANODEA1") (class "Default")
      (node (ref "LEVEL2-IO35") (pin "2") (pinfunction "S_2") (pintype "passive"))
      (node (ref "RN4") (pin "6") (pinfunction "2_6") (pintype "passive"))
    )
    (net (code "7") (name "ANODEA2") (class "Default")
      (node (ref "LEVEL4-IO36") (pin "2") (pinfunction "S_2") (pintype "passive"))
      (node (ref "RN4") (pin "7") (pinfunction "2_7") (pintype "passive"))
    )
    (net (code "8") (name "ANODEA3") (class "Default")
      (node (ref "LEVEL3-IO34") (pin "2") (pinfunction "S_2") (pintype "passive"))
      (node (ref "RN4") (pin "8") (pinfunction "2_8") (pintype "passive"))
    )
    (net (code "9") (name "BTN1") (class "Default")
      (node (ref "BUTTON") (pin "A") (pinfunction "P_A") (pintype "passive"))
      (node (ref "BUTTON") (pin "A'") (pinfunction "P1_A'") (pintype "passive"))
      (node (ref "R15") (pin "1") (pinfunction "1_1") (pintype "passive"))
      (node (ref "U$3") (pin "TDI") (pinfunction "IO12_TDI") (pintype "bidirectional"))
    )
    (net (code "10") (name "CS") (class "Default")
      (node (ref "J9") (pin "1") (pinfunction "1_1") (pintype "passive"))
    )
    (net (code "13") (name "FANCOUNTER") (class "Default")
      (node (ref "IO0") (pin "1") (pinfunction "1_1") (pintype "passive"))
      (node (ref "IO32") (pin "1") (pinfunction "1_1") (pintype "passive"))
      (node (ref "J1") (pin "3") (pinfunction "3_3") (pintype "passive"))
    )
    (net (code "14") (name "FANGND") (class "Default")
      (node (ref "J1") (pin "1") (pinfunction "1_1") (pintype "passive"))
      (node (ref "Q5") (pin "2") (pinfunction "D_2") (pintype "passive"))
      (node (ref "Q5") (pin "4") (pinfunction "D2_4") (pintype "passive"))
    )
    (net (code "15") (name "FANPWM") (class "Default")
      (node (ref "Q5") (pin "1") (pinfunction "G_1") (pintype "passive"))
      (node (ref "R14") (pin "1") (pinfunction "1_1") (pintype "passive"))
      (node (ref "U$3") (pin "IO16") (pinfunction "IO16_IO16") (pintype "bidirectional"))
    )
    (net (code "16") (name "GND") (class "Default")
      (node (ref "74LVC1") (pin "2") (pinfunction "GND_2") (pintype "power_in"))
      (node (ref "C1") (pin "2") (pinfunction "2_2") (pintype "passive"))
      (node (ref "C10") (pin "1") (pinfunction "1_1") (pintype "passive"))
      (node (ref "C11") (pin "2") (pinfunction "2_2") (pintype "passive"))
      (node (ref "C12") (pin "2") (pinfunction "2_2") (pintype "passive"))
      (node (ref "C13") (pin "1") (pinfunction "1_1") (pintype "passive"))
      (node (ref "C14") (pin "2") (pinfunction "2_2") (pintype "passive"))
      (node (ref "C2") (pin "2") (pinfunction "2_2") (pintype "passive"))
      (node (ref "C3") (pin "1") (pinfunction "1_1") (pintype "passive"))
      (node (ref "C4") (pin "2") (pinfunction "2_2") (pintype "passive"))
      (node (ref "C5") (pin "2") (pinfunction "2_2") (pintype "passive"))
      (node (ref "C6") (pin "2") (pinfunction "2_2") (pintype "passive"))
      (node (ref "C7") (pin "2") (pinfunction "2_2") (pintype "passive"))
      (node (ref "C8") (pin "1") (pinfunction "1_1") (pintype "passive"))
      (node (ref "C9") (pin "2") (pinfunction "2_2") (pintype "passive"))
      (node (ref "CN1") (pin "3") (pinfunction "1_3") (pintype "passive"))
      (node (ref "CN1") (pin "4") (pinfunction "1_4") (pintype "passive"))
      (node (ref "CN1") (pin "7") (pinfunction "2_7") (pintype "passive"))
      (node (ref "CN1") (pin "8") (pinfunction "2_8") (pintype "passive"))
      (node (ref "CONN1") (pin "1") (pinfunction "GND_1") (pintype "passive"))
      (node (ref "CONN1") (pin "MT1") (pinfunction "MT_MT1") (pintype "bidirectional"))
      (node (ref "CONN1") (pin "MT2") (pinfunction "MT_MT2") (pintype "bidirectional"))
      (node (ref "CONN2") (pin "1") (pinfunction "GND_1") (pintype "passive"))
      (node (ref "CONN2") (pin "MT1") (pinfunction "MT_MT1") (pintype "bidirectional"))
      (node (ref "CONN2") (pin "MT2") (pinfunction "MT_MT2") (pintype "bidirectional"))
      (node (ref "IC1") (pin "2") (pinfunction "GND_2") (pintype "power_in"))
      (node (ref "IC1") (pin "5") (pinfunction "GND_5") (pintype "power_in"))
      (node (ref "J10") (pin "2") (pinfunction "2_2") (pintype "passive"))
      (node (ref "J11") (pin "2") (pinfunction "2_2") (pintype "passive"))
      (node (ref "J11") (pin "3") (pinfunction "3_3") (pintype "passive"))
      (node (ref "J12") (pin "4") (pinfunction "4_4") (pintype "passive"))
      (node (ref "J2") (pin "1") (pinfunction "1_1") (pintype "passive"))
      (node (ref "J3") (pin "1") (pinfunction "1_1") (pintype "passive"))
      (node (ref "J4") (pin "1") (pinfunction "1_1") (pintype "passive"))
      (node (ref "J5") (pin "1") (pinfunction "1_1") (pintype "passive"))
      (node (ref "J6") (pin "2") (pinfunction "2_2") (pintype "passive"))
      (node (ref "J7") (pin "2") (pinfunction "2_2") (pintype "passive"))
      (node (ref "J8") (pin "2") (pinfunction "2_2") (pintype "passive"))
      (node (ref "J9") (pin "5") (pinfunction "5_5") (pintype "passive"))
      (node (ref "JP14") (pin "2") (pinfunction "2_2") (pintype "passive"))
      (node (ref "K1") (pin "3") (pinfunction "3_3") (pintype "passive"))
      (node (ref "LEVEL1-IO39") (pin "4") (pinfunction "S_4") (pintype "passive"))
      (node (ref "LEVEL2-IO35") (pin "4") (pinfunction "S_4") (pintype "passive"))
      (node (ref "LEVEL3-IO34") (pin "4") (pinfunction "S_4") (pintype "passive"))
      (node (ref "LEVEL4-IO36") (pin "4") (pinfunction "S_4") (pintype "passive"))
      (node (ref "Q1") (pin "3") (pinfunction "S_3") (pintype "passive"))
      (node (ref "Q2") (pin "3") (pinfunction "S_3") (pintype "passive"))
      (node (ref "Q3") (pin "3") (pinfunction "S_3") (pintype "passive"))
      (node (ref "Q4") (pin "3") (pinfunction "S_3") (pintype "passive"))
      (node (ref "Q5") (pin "3") (pinfunction "S_3") (pintype "passive"))
      (node (ref "R1") (pin "2") (pinfunction "2_2") (pintype "passive"))
      (node (ref "R15") (pin "2") (pinfunction "2_2") (pintype "passive"))
      (node (ref "R2") (pin "2") (pinfunction "2_2") (pintype "passive"))
      (node (ref "R4") (pin "1") (pinfunction "1_1") (pintype "passive"))
      (node (ref "RN2") (pin "1") (pinfunction "1_1") (pintype "passive"))
      (node (ref "RN2") (pin "2") (pinfunction "1_2") (pintype "passive"))
      (node (ref "RN2") (pin "3") (pinfunction "1_3") (pintype "passive"))
      (node (ref "RN2") (pin "4") (pinfunction "1_4") (pintype "passive"))
      (node (ref "SERVO1") (pin "1") (pinfunction "1_1") (pintype "passive"))
      (node (ref "SERVO2") (pin "1") (pinfunction "1_1") (pintype "passive"))
      (node (ref "SERVO3") (pin "1") (pinfunction "1_1") (pintype "passive"))
      (node (ref "SERVO4") (pin "1") (pinfunction "1_1") (pintype "passive"))
      (node (ref "U$3") (pin "GND") (pinfunction "GND_GND") (pintype "bidirectional"))
      (node (ref "U$3") (pin "GND2") (pinfunction "GND_GND2") (pintype "bidirectional"))
      (node (ref "U$3") (pin "GND3") (pinfunction "GND_GND3") (pintype "bidirectional"))
      (node (ref "U$5") (pin "P$1") (pinfunction "P$1_P$1") (pintype "bidirectional"))
      (node (ref "U$6") (pin "P$1") (pinfunction "P$1_P$1") (pintype "bidirectional"))
      (node (ref "U$7") (pin "1") (pinfunction "GND_1") (pintype "input"))
      (node (ref "U$8") (pin "P$1") (pinfunction "GND_P$1") (pintype "bidirectional"))
      (node (ref "U$8") (pin "P$2") (pinfunction "GND_P$2") (pintype "bidirectional"))
      (node (ref "U$9") (pin "P$1") (pinfunction "P$1_P$1") (pintype "bidirectional"))
      (node (ref "ULN1") (pin "9") (pinfunction "9_9") (pintype "bidirectional"))
      (node (ref "X5") (pin "2") (pinfunction "S_2") (pintype "passive"))
      (node (ref "X7") (pin "1") (pinfunction "S_1") (pintype "passive"))
    )
    (net (code "20") (name "IO0") (class "Default")
      (node (ref "IO0") (pin "2") (pinfunction "2_2") (pintype "passive"))
      (node (ref "R10") (pin "1") (pinfunction "1_1") (pintype "passive"))
      (node (ref "U$3") (pin "IO0") (pinfunction "IO0_IO0") (pintype "bidirectional"))
    )
    (net (code "21") (name "IO4") (class "Default")
      (node (ref "R12") (pin "1") (pinfunction "1_1") (pintype "passive"))
      (node (ref "RGB") (pin "3") (pinfunction "3_3") (pintype "passive"))
      (node (ref "U$3") (pin "IO4") (pinfunction "IO4_IO4") (pintype "bidirectional"))
    )
    (net (code "22") (name "IO14") (class "Default")
      (node (ref "IO14") (pin "2") (pinfunction "2_2") (pintype "passive"))
      (node (ref "R11") (pin "1") (pinfunction "1_1") (pintype "passive"))
      (node (ref "U$3") (pin "TMS") (pinfunction "IO14_TMS") (pintype "bidirectional"))
    )
    (net (code "23") (name "IO15") (class "Default")
      (node (ref "IO15") (pin "2") (pinfunction "2_2") (pintype "passive"))
      (node (ref "R8") (pin "1") (pinfunction "1_1") (pintype "passive"))
      (node (ref "U$3") (pin "TD0") (pinfunction "IO15_TD0") (pintype "bidirectional"))
    )
    (net (code "24") (name "IO25") (class "Default")
      (node (ref "IO25") (pin "2") (pinfunction "2_2") (pintype "passive"))
      (node (ref "R23") (pin "1") (pinfunction "1_1") (pintype "passive"))
      (node (ref "U$3") (pin "IO25") (pinfunction "IO25_IO25") (pintype "bidirectional"))
    )
    (net (code "25") (name "IO27") (class "Default")
      (node (ref "IO27") (pin "2") (pinfunction "2_2") (pintype "passive"))
      (node (ref "R24") (pin "1") (pinfunction "1_1") (pintype "passive"))
      (node (ref "U$3") (pin "IO27") (pinfunction "IO27_IO27") (pintype "bidirectional"))
    )
    (net (code "26") (name "IO32") (class "Default")
      (node (ref "IO32") (pin "2") (pinfunction "2_2") (pintype "passive"))
      (node (ref "R19") (pin "1") (pinfunction "1_1") (pintype "passive"))
      (node (ref "U$3") (pin "IO32") (pinfunction "IO32_IO32") (pintype "bidirectional"))
    )
    (net (code "27") (name "IO33") (class "Default")
      (node (ref "IO33") (pin "2") (pinfunction "2_2") (pintype "passive"))
      (node (ref "R20") (pin "1") (pinfunction "1_1") (pintype "passive"))
      (node (ref "U$3") (pin "IO33") (pinfunction "IO33_IO33") (pintype "bidirectional"))
    )
    (net (code "28") (name "LED") (class "Default")
      (node (ref "R3") (pin "1") (pinfunction "1_1") (pintype "passive"))
      (node (ref "U$3") (pin "IO2") (pinfunction "IO2_IO2") (pintype "bidirectional"))
    )
    (net (code "29") (name "LEDVCC") (class "Default")
      (node (ref "J4") (pin "3") (pinfunction "3_3") (pintype "passive"))
      (node (ref "JP3") (pin "1") (pinfunction "1_1") (pintype "passive"))
      (node (ref "JP8") (pin "1") (pinfunction "1_1") (pintype "passive"))
    )
    (net (code "30") (name "LEVEL1") (class "Default")
      (node (ref "CN1") (pin "5") (pinfunction "2_5") (pintype "passive"))
      (node (ref "LEVEL1-IO39") (pin "3") (pinfunction "S_3") (pintype "passive"))
      (node (ref "RN2") (pin "5") (pinfunction "2_5") (pintype "passive"))
      (node (ref "U$3") (pin "SVN") (pinfunction "IO39_SVN") (pintype "bidirectional"))
    )
    (net (code "31") (name "LEVEL2") (class "Default")
      (node (ref "CN1") (pin "6") (pinfunction "2_6") (pintype "passive"))
      (node (ref "LEVEL2-IO35") (pin "3") (pinfunction "S_3") (pintype "passive"))
      (node (ref "RN2") (pin "6") (pinfunction "2_6") (pintype "passive"))
      (node (ref "U$3") (pin "IO35") (pinfunction "IO35_IO35") (pintype "bidirectional"))
    )
    (net (code "32") (name "LEVEL3") (class "Default")
      (node (ref "CN1") (pin "2") (pinfunction "1_2") (pintype "passive"))
      (node (ref "LEVEL4-IO36") (pin "3") (pinfunction "S_3") (pintype "passive"))
      (node (ref "RN2") (pin "7") (pinfunction "2_7") (pintype "passive"))
      (node (ref "U$3") (pin "IO34") (pinfunction "IO34_IO34") (pintype "bidirectional"))
    )
    (net (code "33") (name "LEVEL4") (class "Default")
      (node (ref "CN1") (pin "1") (pinfunction "1_1") (pintype "passive"))
      (node (ref "LEVEL3-IO34") (pin "3") (pinfunction "S_3") (pintype "passive"))
      (node (ref "RN2") (pin "8") (pinfunction "2_8") (pintype "passive"))
      (node (ref "U$3") (pin "SVP") (pinfunction "IO36_SVP") (pintype "bidirectional"))
    )
    (net (code "34") (name "LIMIT1") (class "Default")
      (node (ref "IO14") (pin "3") (pinfunction "3_3") (pintype "passive"))
      (node (ref "IO25") (pin "3") (pinfunction "3_3") (pintype "passive"))
      (node (ref "J7") (pin "1") (pinfunction "1_1") (pintype "passive"))
    )
    (net (code "35") (name "LIMIT2") (class "Default")
      (node (ref "IO32") (pin "3") (pinfunction "3_3") (pintype "passive"))
      (node (ref "IO33") (pin "3") (pinfunction "3_3") (pintype "passive"))
      (node (ref "J8") (pin "1") (pinfunction "1_1") (pintype "passive"))
    )
    (net (code "36") (name "MOSFETGND1") (class "Default")
      (node (ref "Q1") (pin "2") (pinfunction "D_2") (pintype "passive"))
      (node (ref "Q1") (pin "4") (pinfunction "D2_4") (pintype "passive"))
      (node (ref "X1") (pin "2") (pinfunction "S_2") (pintype "passive"))
    )
    (net (code "37") (name "MOSFETGND2") (class "Default")
      (node (ref "Q2") (pin "2") (pinfunction "D_2") (pintype "passive"))
      (node (ref "Q2") (pin "4") (pinfunction "D2_4") (pintype "passive"))
      (node (ref "X2") (pin "2") (pinfunction "S_2") (pintype "passive"))
    )
    (net (code "38") (name "MOSFETGND3") (class "Default")
      (node (ref "Q3") (pin "2") (pinfunction "D_2") (pintype "passive"))
      (node (ref "Q3") (pin "4") (pinfunction "D2_4") (pintype "passive"))
      (node (ref "X3") (pin "2") (pinfunction "S_2") (pintype "passive"))
    )
    (net (code "39") (name "MOSFETGND4") (class "Default")
      (node (ref "Q4") (pin "2") (pinfunction "D_2") (pintype "passive"))
      (node (ref "Q4") (pin "4") (pinfunction "D2_4") (pintype "passive"))
      (node (ref "X4") (pin "2") (pinfunction "S_2") (pintype "passive"))
    )
    (net (code "40") (name "MOSFETVCC1") (class "Default")
      (node (ref "C5") (pin "1") (pinfunction "1_1") (pintype "passive"))
      (node (ref "C8") (pin "2") (pinfunction "2_2") (pintype "passive"))
      (node (ref "JP1") (pin "1") (pinfunction "1_1") (pintype "passive"))
      (node (ref "JP4") (pin "1") (pinfunction "1_1") (pintype "passive"))
      (node (ref "JP5") (pin "1") (pinfunction "1_1") (pintype "passive"))
      (node (ref "SERVO1") (pin "2") (pinfunction "2_2") (pintype "passive"))
      (node (ref "X1") (pin "1") (pinfunction "S_1") (pintype "passive"))
      (node (ref "X2") (pin "1") (pinfunction "S_1") (pintype "passive"))
    )
    (net (code "41") (name "MOSFETVCC2") (class "Default")
      (node (ref "C10") (pin "2") (pinfunction "2_2") (pintype "passive"))
      (node (ref "C6") (pin "1") (pinfunction "1_1") (pintype "passive"))
      (node (ref "J1") (pin "2") (pinfunction "2_2") (pintype "passive"))
      (node (ref "JP1") (pin "2") (pinfunction "2_2") (pintype "passive"))
      (node (ref "JP6") (pin "1") (pinfunction "1_1") (pintype "passive"))
      (node (ref "JP7") (pin "1") (pinfunction "1_1") (pintype "passive"))
      (node (ref "SERVO2") (pin "2") (pinfunction "2_2") (pintype "passive"))
      (node (ref "X3") (pin "1") (pinfunction "S_1") (pintype "passive"))
      (node (ref "X4") (pin "1") (pinfunction "S_1") (pintype "passive"))
    )
    (net (code "42") (name "Net-(3V3OK-PadC)") (class "Default")
      (node (ref "3V3OK") (pin "C") (pinfunction "C_C") (pintype "passive"))
      (node (ref "R1") (pin "1") (pinfunction "1_1") (pintype "passive"))
    )
    (net (code "43") (name "Net-(5VOK-PadC)") (class "Default")
      (node (ref "5VOK") (pin "C") (pinfunction "C_C") (pintype "passive"))
      (node (ref "R2") (pin "1") (pinfunction "1_1") (pintype "passive"))
    )
    (net (code "44") (name "Net-(74LVC1-B)") (class "Default")
      (node (ref "74LVC1") (pin "4") (pinfunction "B_4") (pintype "bidirectional"))
      (node (ref "R7") (pin "2") (pinfunction "2_2") (pintype "passive"))
    )
    (net (code "45") (name "Net-(74LVC1-DIR)") (class "Default")
      (node (ref "74LVC1") (pin "5") (pinfunction "DIR_5") (pintype "input"))
      (node (ref "R6") (pin "2") (pinfunction "2_2") (pintype "passive"))
    )
    (net (code "46") (name "Net-(R3-Pad2)") (class "Default")
      (node (ref "R3") (pin "2") (pinfunction "2_2") (pintype "passive"))
      (node (ref "STATUS") (pin "C") (pinfunction "C_C") (pintype "passive"))
    )
    (net (code "47") (name "Net-(RN3-Pad1)") (class "Default")
      (node (ref "RN3") (pin "1") (pinfunction "1_1") (pintype "passive"))
      (node (ref "S4") (pin "A") (pinfunction "A_A") (pintype "passive"))
    )
    (net (code "48") (name "Net-(RN3B-1)") (class "Default")
      (node (ref "RN3") (pin "2") (pinfunction "1_2") (pintype "passive"))
      (node (ref "S3") (pin "A") (pinfunction "A_A") (pintype "passive"))
    )
    (net (code "49") (name "Net-(RN3C-1)") (class "Default")
      (node (ref "RN3") (pin "3") (pinfunction "1_3") (pintype "passive"))
      (node (ref "S2") (pin "A") (pinfunction "A_A") (pintype "passive"))
    )
    (net (code "50") (name "Net-(RN3D-1)") (class "Default")
      (node (ref "RN3") (pin "4") (pinfunction "1_4") (pintype "passive"))
      (node (ref "S1") (pin "A") (pinfunction "A_A") (pintype "passive"))
    )
    (net (code "52") (name "PIO1") (class "Default")
      (node (ref "Q1") (pin "1") (pinfunction "G_1") (pintype "passive"))
      (node (ref "R18") (pin "1") (pinfunction "1_1") (pintype "passive"))
      (node (ref "SERVO1") (pin "3") (pinfunction "3_3") (pintype "passive"))
      (node (ref "U$3") (pin "IO19") (pinfunction "IO19_IO19") (pintype "bidirectional"))
    )
    (net (code "53") (name "PIO2") (class "Default")
      (node (ref "Q2") (pin "1") (pinfunction "G_1") (pintype "passive"))
      (node (ref "R16") (pin "1") (pinfunction "1_1") (pintype "passive"))
      (node (ref "U$3") (pin "IO23") (pinfunction "IO23_IO23") (pintype "bidirectional"))
    )
    (net (code "54") (name "PIO3") (class "Default")
      (node (ref "Q3") (pin "1") (pinfunction "G_1") (pintype "passive"))
      (node (ref "R13") (pin "1") (pinfunction "1_1") (pintype "passive"))
      (node (ref "SERVO2") (pin "3") (pinfunction "3_3") (pintype "passive"))
      (node (ref "U$3") (pin "IO5") (pinfunction "IO5_IO5") (pintype "bidirectional"))
    )
    (net (code "55") (name "PIO4") (class "Default")
      (node (ref "Q4") (pin "1") (pinfunction "G_1") (pintype "passive"))
      (node (ref "R9") (pin "1") (pinfunction "1_1") (pintype "passive"))
      (node (ref "RGB") (pin "1") (pinfunction "1_1") (pintype "passive"))
      (node (ref "U$3") (pin "TCK") (pinfunction "IO13_TCK") (pintype "bidirectional"))
    )
    (net (code "56") (name "RGB3V3") (class "Default")
      (node (ref "74LVC1") (pin "3") (pinfunction "A_3") (pintype "bidirectional"))
      (node (ref "RGB") (pin "2") (pinfunction "2_2") (pintype "passive"))
    )
    (net (code "57") (name "RGB5V") (class "Default")
      (node (ref "J4") (pin "2") (pinfunction "2_2") (pintype "passive"))
      (node (ref "R7") (pin "1") (pinfunction "1_1") (pintype "passive"))
    )
    (net (code "58") (name "RST") (class "Default")
      (node (ref "U$3") (pin "RST") (pinfunction "RST_RST") (pintype "bidirectional"))
    )
    (net (code "59") (name "SCL") (class "Default")
      (node (ref "CONN1") (pin "4") (pinfunction "SCL_4") (pintype "passive"))
      (node (ref "CONN2") (pin "4") (pinfunction "SCL_4") (pintype "passive"))
      (node (ref "IC1") (pin "6") (pinfunction "BUS1_6") (pintype "bidirectional"))
      (node (ref "J12") (pin "1") (pinfunction "1_1") (pintype "passive"))
      (node (ref "J9") (pin "4") (pinfunction "4_4") (pintype "passive"))
      (node (ref "K1") (pin "2") (pinfunction "2_2") (pintype "passive"))
      (node (ref "R22") (pin "2") (pinfunction "2_2") (pintype "passive"))
      (node (ref "U$3") (pin "IO22") (pinfunction "IO22_IO22") (pintype "bidirectional"))
    )
    (net (code "60") (name "SD0") (class "Default")
      (node (ref "J9") (pin "2") (pinfunction "2_2") (pintype "passive"))
      (node (ref "JP14") (pin "1") (pinfunction "1_1") (pintype "passive"))
    )
    (net (code "61") (name "SDA") (class "Default")
      (node (ref "CONN1") (pin "3") (pinfunction "SDA_3") (pintype "passive"))
      (node (ref "CONN2") (pin "3") (pinfunction "SDA_3") (pintype "passive"))
      (node (ref "IC1") (pin "4") (pinfunction "BUS2_4") (pintype "bidirectional"))
      (node (ref "J12") (pin "2") (pinfunction "2_2") (pintype "passive"))
      (node (ref "J9") (pin "3") (pinfunction "3_3") (pintype "passive"))
      (node (ref "K1") (pin "1") (pinfunction "1_1") (pintype "passive"))
      (node (ref "R21") (pin "2") (pinfunction "2_2") (pintype "passive"))
      (node (ref "U$3") (pin "IO21") (pinfunction "IO21_IO21") (pintype "bidirectional"))
    )
    (net (code "62") (name "SERVO1") (class "Default")
      (node (ref "IO14") (pin "1") (pinfunction "1_1") (pintype "passive"))
      (node (ref "IO27") (pin "3") (pinfunction "3_3") (pintype "passive"))
      (node (ref "SERVO4") (pin "3") (pinfunction "3_3") (pintype "passive"))
    )
    (net (code "63") (name "SERVO2") (class "Default")
      (node (ref "IO15") (pin "3") (pinfunction "3_3") (pintype "passive"))
      (node (ref "IO33") (pin "1") (pinfunction "1_1") (pintype "passive"))
      (node (ref "SERVO3") (pin "3") (pinfunction "3_3") (pintype "passive"))
    )
    (net (code "64") (name "SERVOVCC") (class "Default")
      (node (ref "JP11") (pin "1") (pinfunction "1_1") (pintype "passive"))
      (node (ref "JP12") (pin "1") (pinfunction "1_1") (pintype "passive"))
      (node (ref "JP13") (pin "1") (pinfunction "1_1") (pintype "passive"))
      (node (ref "SERVO3") (pin "2") (pinfunction "2_2") (pintype "passive"))
      (node (ref "SERVO4") (pin "2") (pinfunction "2_2") (pintype "passive"))
    )
    (net (code "65") (name "STEPPER1") (class "Default")
      (node (ref "S1") (pin "C") (pinfunction "C_C") (pintype "passive"))
      (node (ref "ULN1") (pin "17") (pinfunction "17_17") (pintype "bidirectional"))
      (node (ref "ULN1") (pin "18") (pinfunction "18_18") (pintype "bidirectional"))
      (node (ref "X8") (pin "2") (pinfunction "S_2") (pintype "passive"))
    )
    (net (code "66") (name "STEPPER2") (class "Default")
      (node (ref "S2") (pin "C") (pinfunction "C_C") (pintype "passive"))
      (node (ref "ULN1") (pin "15") (pinfunction "15_15") (pintype "bidirectional"))
      (node (ref "ULN1") (pin "16") (pinfunction "16_16") (pintype "bidirectional"))
      (node (ref "X8") (pin "3") (pinfunction "S_3") (pintype "passive"))
    )
    (net (code "67") (name "STEPPER3") (class "Default")
      (node (ref "S3") (pin "C") (pinfunction "C_C") (pintype "passive"))
      (node (ref "ULN1") (pin "13") (pinfunction "13_13") (pintype "bidirectional"))
      (node (ref "ULN1") (pin "14") (pinfunction "14_14") (pintype "bidirectional"))
      (node (ref "X8") (pin "4") (pinfunction "S_4") (pintype "passive"))
    )
    (net (code "68") (name "STEPPER4") (class "Default")
      (node (ref "S4") (pin "C") (pinfunction "C_C") (pintype "passive"))
      (node (ref "ULN1") (pin "11") (pinfunction "11_11") (pintype "bidirectional"))
      (node (ref "ULN1") (pin "12") (pinfunction "12_12") (pintype "bidirectional"))
      (node (ref "X8") (pin "5") (pinfunction "S_5") (pintype "passive"))
    )
    (net (code "69") (name "STEPPERA") (class "Default")
      (node (ref "IO27") (pin "1") (pinfunction "1_1") (pintype "passive"))
      (node (ref "RN1") (pin "4") (pinfunction "1_4") (pintype "passive"))
      (node (ref "ULN1") (pin "1") (pinfunction "1_1") (pintype "bidirectional"))
      (node (ref "ULN1") (pin "2") (pinfunction "2_2") (pintype "bidirectional"))
    )
    (net (code "70") (name "STEPPERB") (class "Default")
      (node (ref "IO25") (pin "1") (pinfunction "1_1") (pintype "passive"))
      (node (ref "RN1") (pin "3") (pinfunction "1_3") (pintype "passive"))
      (node (ref "ULN1") (pin "3") (pinfunction "3_3") (pintype "bidirectional"))
      (node (ref "ULN1") (pin "4") (pinfunction "4_4") (pintype "bidirectional"))
    )
    (net (code "71") (name "STEPPERC") (class "Default")
      (node (ref "IO0") (pin "3") (pinfunction "3_3") (pintype "passive"))
      (node (ref "RN1") (pin "2") (pinfunction "1_2") (pintype "passive"))
      (node (ref "ULN1") (pin "5") (pinfunction "5_5") (pintype "bidirectional"))
      (node (ref "ULN1") (pin "6") (pinfunction "6_6") (pintype "bidirectional"))
    )
    (net (code "72") (name "STEPPERD") (class "Default")
      (node (ref "IO15") (pin "1") (pinfunction "1_1") (pintype "passive"))
      (node (ref "RN1") (pin "1") (pinfunction "1_1") (pintype "passive"))
      (node (ref "ULN1") (pin "7") (pinfunction "7_7") (pintype "bidirectional"))
      (node (ref "ULN1") (pin "8") (pinfunction "8_8") (pintype "bidirectional"))
    )
    (net (code "75") (name "STEPPERVCC") (class "Default")
      (node (ref "JP10") (pin "1") (pinfunction "1_1") (pintype "passive"))
      (node (ref "JP9") (pin "1") (pinfunction "1_1") (pintype "passive"))
      (node (ref "ULN1") (pin "10") (pinfunction "10_10") (pintype "bidirectional"))
      (node (ref "X8") (pin "1") (pinfunction "S_1") (pintype "passive"))
    )
    (net (code "76") (name "TURBINETACH") (class "Default")
      (node (ref "R5") (pin "2") (pinfunction "2_2") (pintype "passive"))
      (node (ref "U$3") (pin "IO18") (pinfunction "IO18_IO18") (pintype "bidirectional"))
      (node (ref "X7") (pin "2") (pinfunction "S_2") (pintype "passive"))
    )
    (net (code "77") (name "TURBINETHERM") (class "Default")
      (node (ref "R4") (pin "2") (pinfunction "2_2") (pintype "passive"))
      (node (ref "U$3") (pin "IO26") (pinfunction "IO26_IO26") (pintype "bidirectional"))
      (node (ref "X6") (pin "1") (pinfunction "S_1") (pintype "passive"))
    )
    (net (code "78") (name "VIN1") (class "Default")
      (node (ref "C13") (pin "2") (pinfunction "2_2") (pintype "passive"))
      (node (ref "C9") (pin "1") (pinfunction "1_1") (pintype "passive"))
      (node (ref "J10") (pin "1") (pinfunction "1_1") (pintype "passive"))
      (node (ref "J11") (pin "4") (pinfunction "4_4") (pintype "passive"))
      (node (ref "J6") (pin "1") (pinfunction "1_1") (pintype "passive"))
      (node (ref "JP10") (pin "2") (pinfunction "2_2") (pintype "passive"))
      (node (ref "JP11") (pin "2") (pinfunction "2_2") (pintype "passive"))
      (node (ref "JP4") (pin "2") (pinfunction "2_2") (pintype "passive"))
      (node (ref "U$10") (pin "P$1") (pinfunction "P$1_P$1") (pintype "bidirectional"))
      (node (ref "U$8") (pin "P$3") (pinfunction "VUSBPD_P$3") (pintype "bidirectional"))
      (node (ref "U$8") (pin "P$4") (pinfunction "VUSBPD_P$4") (pintype "bidirectional"))
    )
    (net (code "79") (name "VIN2") (class "Default")
      (node (ref "J3") (pin "2") (pinfunction "2_2") (pintype "passive"))
      (node (ref "JP3") (pin "2") (pinfunction "2_2") (pintype "passive"))
      (node (ref "JP7") (pin "2") (pinfunction "2_2") (pintype "passive"))
      (node (ref "U$4") (pin "P$1") (pinfunction "P$1_P$1") (pintype "bidirectional"))
    )
    (net (code "80") (name "unconnected-(U$3-IO06-PadCLK)") (class "Default")
      (node (ref "U$3") (pin "CLK") (pinfunction "IO06_CLK") (pintype "bidirectional"))
    )
    (net (code "81") (name "unconnected-(U$3-IO07-PadSD0)") (class "Default")
      (node (ref "U$3") (pin "SD0") (pinfunction "IO07_SD0") (pintype "bidirectional"))
    )
    (net (code "82") (name "unconnected-(U$3-IO08-PadSD1)") (class "Default")
      (node (ref "U$3") (pin "SD1") (pinfunction "IO08_SD1") (pintype "bidirectional"))
    )
    (net (code "83") (name "unconnected-(U$3-IO09-PadSD2)") (class "Default")
      (node (ref "U$3") (pin "SD2") (pinfunction "IO09_SD2") (pintype "bidirectional"))
    )
    (net (code "84") (name "unconnected-(U$3-IO10-PadSD3)") (class "Default")
      (node (ref "U$3") (pin "SD3") (pinfunction "IO10_SD3") (pintype "bidirectional"))
    )
    (net (code "85") (name "unconnected-(U$3-IO11-PadCMD)") (class "Default")
      (node (ref "U$3") (pin "CMD") (pinfunction "IO11_CMD") (pintype "bidirectional"))
    )
    (net (code "86") (name "unconnected-(U$3-NC-PadNC2)") (class "Default")
      (node (ref "U$3") (pin "NC2") (pinfunction "NC_NC2") (pintype "bidirectional"))
    )
    (net (code "87") (name "unconnected-(U$3-PadNC)") (class "Default")
      (node (ref "U$3") (pin "NC") (pinfunction "NC_NC") (pintype "bidirectional"))
    )
    (net (code "88") (name "unconnected-(U$3-PadRXD)") (class "Default")
      (node (ref "U$3") (pin "RXD") (pinfunction "RXD_RXD") (pintype "bidirectional"))
    )
    (net (code "89") (name "unconnected-(U$3-PadTXD)") (class "Default")
      (node (ref "U$3") (pin "TXD") (pinfunction "TXD_TXD") (pintype "bidirectional"))
    )
  )
)
